# fat41.net
KiCad netlist of a schematic drawn in Altium Designer
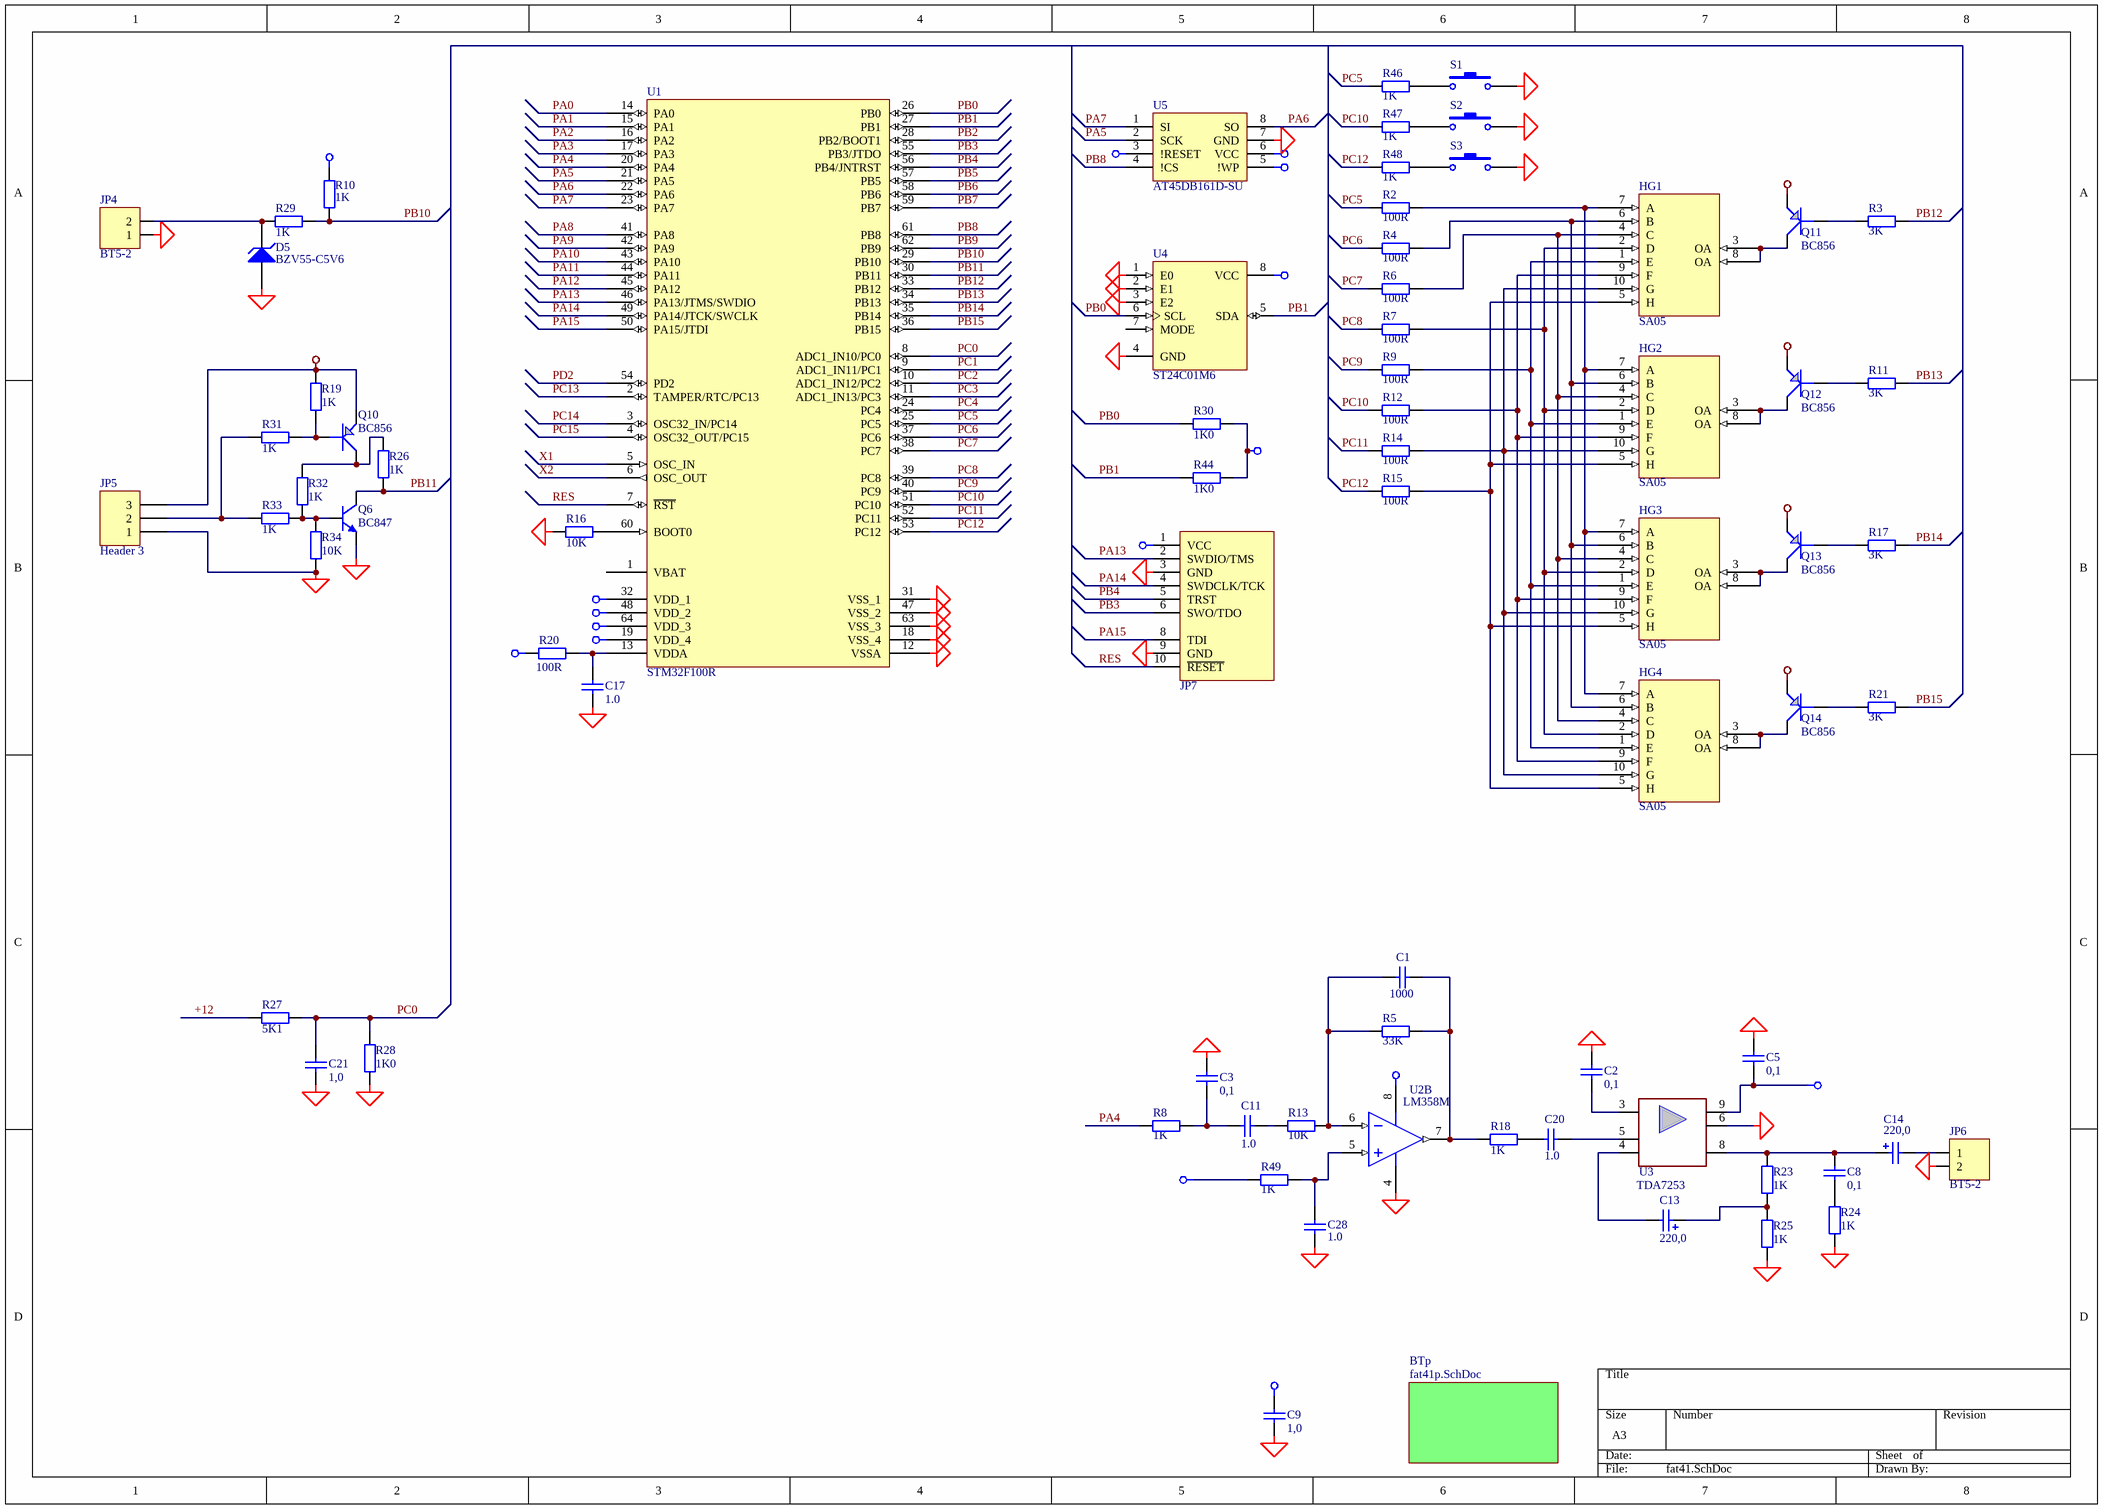
[diagram p0: fat41.SchDoc]

(export (version "E")
  (design (tool "Eeschema 10.0.6"))
  (components
    (comp (ref "C1")
      (value "Cap Semi")
      (footprint "_1206")
      (description "Capacitor (Semiconductor SIM Model)")
      (fields
        (field (name "MANUFACTURER") "Generic Components")
        (field (name "ALTIUM_VALUE") "1000")
        (field (name "PUBLISHER") "Altium Limited")
      )
      (libsource (lib "Miscellaneous Devices") (part "Cap Semi"))
    )
    (comp (ref "C2")
      (value "Cap Semi")
      (footprint "C3216-1206")
      (description "Capacitor (Semiconductor SIM Model)")
      (fields
        (field (name "MANUFACTURER") "Generic Components")
        (field (name "ALTIUM_VALUE") "0,1")
        (field (name "PUBLISHER") "Altium Limited")
      )
      (libsource (lib "Miscellaneous Devices") (part "Cap Semi"))
    )
    (comp (ref "C3")
      (value "Cap Semi")
      (footprint "_1206")
      (description "Capacitor (Semiconductor SIM Model)")
      (fields
        (field (name "MANUFACTURER") "Generic Components")
        (field (name "ALTIUM_VALUE") "0,1")
        (field (name "PUBLISHER") "Altium Limited")
      )
      (libsource (lib "") (part "Cap Semi_1"))
    )
    (comp (ref "C5")
      (value "Cap Semi")
      (footprint "C3216-1206")
      (description "Capacitor (Semiconductor SIM Model)")
      (fields
        (field (name "MANUFACTURER") "Generic Components")
        (field (name "ALTIUM_VALUE") "0,1")
        (field (name "PUBLISHER") "Altium Limited")
      )
      (libsource (lib "Miscellaneous Devices") (part "Cap Semi"))
    )
    (comp (ref "C8")
      (value "Cap Semi")
      (footprint "C3216-1206")
      (description "Capacitor (Semiconductor SIM Model)")
      (fields
        (field (name "MANUFACTURER") "Generic Components")
        (field (name "ALTIUM_VALUE") "0,1")
        (field (name "PUBLISHER") "Altium Limited")
      )
      (libsource (lib "Miscellaneous Devices") (part "Cap Semi"))
    )
    (comp (ref "C9")
      (value "Cap Semi")
      (footprint "C3216-1206")
      (description "Capacitor (Semiconductor SIM Model)")
      (fields
        (field (name "MANUFACTURER") "Generic Components")
        (field (name "ALTIUM_VALUE") "1,0")
        (field (name "PUBLISHER") "Altium Limited")
      )
      (libsource (lib "Miscellaneous Devices") (part "Cap Semi"))
    )
    (comp (ref "C11")
      (value "Cap Semi")
      (footprint "_1206")
      (description "Capacitor (Semiconductor SIM Model)")
      (fields
        (field (name "MANUFACTURER") "Generic Components")
        (field (name "ALTIUM_VALUE") "1.0")
        (field (name "PUBLISHER") "Altium Limited")
      )
      (libsource (lib "Miscellaneous Devices") (part "Cap Semi"))
    )
    (comp (ref "C13")
      (value "Cap Pol1")
      (footprint "el3")
      (description "Polarized Capacitor (Radial)")
      (fields
        (field (name "MANUFACTURER") "Generic Components")
        (field (name "ALTIUM_VALUE") "220,0")
        (field (name "PUBLISHER") "Altium Limited")
      )
      (libsource (lib "PAL") (part "Cap Pol1"))
    )
    (comp (ref "C14")
      (value "Cap Pol1")
      (footprint "el5")
      (description "Polarized Capacitor (Radial)")
      (fields
        (field (name "MANUFACTURER") "Generic Components")
        (field (name "ALTIUM_VALUE") "220,0")
        (field (name "PUBLISHER") "Altium Limited")
      )
      (libsource (lib "PAL") (part "Cap Pol1"))
    )
    (comp (ref "C17")
      (value "1.0")
      (footprint "_1206")
      (description "Capacitor (Semiconductor SIM Model)")
      (fields (field (name "MANUFACTURER") "Generic Components") (field (name "PUBLISHER") "Altium Limited"))
      (libsource (lib "") (part "Cap Semi_1"))
    )
    (comp (ref "C20")
      (value "Cap Semi")
      (footprint "_1206")
      (description "Capacitor (Semiconductor SIM Model)")
      (fields
        (field (name "MANUFACTURER") "Generic Components")
        (field (name "ALTIUM_VALUE") "1.0")
        (field (name "PUBLISHER") "Altium Limited")
      )
      (libsource (lib "Miscellaneous Devices") (part "Cap Semi"))
    )
    (comp (ref "C21")
      (value "Cap Semi")
      (footprint "_1206")
      (description "Capacitor (Semiconductor SIM Model)")
      (fields
        (field (name "MANUFACTURER") "Generic Components")
        (field (name "ALTIUM_VALUE") "1,0")
        (field (name "PUBLISHER") "Altium Limited")
      )
      (libsource (lib "Miscellaneous Devices") (part "Cap Semi"))
    )
    (comp (ref "C28")
      (value "Cap Semi")
      (footprint "_1206")
      (description "Capacitor (Semiconductor SIM Model)")
      (fields
        (field (name "MANUFACTURER") "Generic Components")
        (field (name "ALTIUM_VALUE") "1.0")
        (field (name "PUBLISHER") "Altium Limited")
      )
      (libsource (lib "") (part "Cap Semi_1"))
    )
    (comp (ref "D5")
      (value "BZV55-C5V6")
      (footprint "_1206d")
      (description "Zener Diode")
      (fields (field (name "MANUFACTURER") "Generic Components") (field (name "PUBLISHER") "Altium Limited"))
      (libsource (lib "Miscellaneous Devices") (part "D Zener"))
    )
    (comp (ref "HG1") (value "SA05") (footprint "DIP10") (libsource (lib "PAL") (part "SA05")))
    (comp (ref "HG2") (value "SA05") (footprint "DIP10") (libsource (lib "PAL") (part "SA05")))
    (comp (ref "HG3") (value "SA05") (footprint "DIP10") (libsource (lib "PAL") (part "SA05")))
    (comp (ref "HG4") (value "SA05") (footprint "DIP10") (libsource (lib "PAL") (part "SA05")))
    (comp (ref "JP4")
      (value "BT5-2")
      (footprint "BT5-2-1")
      (description "Header, 3-Pin")
      (fields (field (name "MANUFACTURER") "Generic Components") (field (name "PUBLISHER") "Altium Limited"))
      (libsource (lib "") (part "BT5-2_1"))
    )
    (comp (ref "JP5")
      (value "Header 3")
      (footprint "BT5-3")
      (description "Header, 3-Pin")
      (fields (field (name "MANUFACTURER") "Generic Components") (field (name "PUBLISHER") "Altium Limited"))
      (libsource (lib "Miscellaneous Connectors") (part "Header 3"))
    )
    (comp (ref "JP6")
      (value "BT5-2")
      (footprint "BT5-2-1")
      (description "Header, 3-Pin")
      (fields (field (name "MANUFACTURER") "Generic Components") (field (name "PUBLISHER") "Altium Limited"))
      (libsource (lib "PAL") (part "BT5-2"))
    )
    (comp (ref "JP7")
      (value "CORTEX_DEBUG_CONNECTOR_PAL")
      (footprint "CORTEX_DEBUG_CONNECTOR")
      (libsource (lib "PAL") (part "CORTEX_DEBUG_CONNECTOR_PAL"))
    )
    (comp (ref "Q6")
      (value "BC847")
      (footprint "SO-G3")
      (description "General Purpose Transistor NPN Silicon")
      (fields (field (name "MANUFACTURER") "Motorola") (field (name "PUBLISHER") "Altium Limited"))
      (libsource (lib "PAL") (part "BC847ALT1"))
    )
    (comp (ref "Q10") (value "BC856") (footprint "SO-G3") (libsource (lib "MAIN") (part "GT109")))
    (comp (ref "Q11") (value "BC856") (footprint "SO-G3") (libsource (lib "MAIN") (part "GT109")))
    (comp (ref "Q12") (value "BC856") (footprint "SO-G3") (libsource (lib "MAIN") (part "GT109")))
    (comp (ref "Q13") (value "BC856") (footprint "SO-G3") (libsource (lib "MAIN") (part "GT109")))
    (comp (ref "Q14") (value "BC856") (footprint "SO-G3") (libsource (lib "MAIN") (part "GT109")))
    (comp (ref "R2")
      (value "Res2")
      (footprint "_1206")
      (description "Resistor")
      (fields
        (field (name "MANUFACTURER") "Generic Components")
        (field (name "ALTIUM_VALUE") "100R")
        (field (name "PUBLISHER") "Altium Limited")
      )
      (libsource (lib "PAL") (part "RES"))
    )
    (comp (ref "R3")
      (value "Res2")
      (footprint "_1206")
      (description "Resistor")
      (fields
        (field (name "MANUFACTURER") "Generic Components")
        (field (name "ALTIUM_VALUE") "3K")
        (field (name "PUBLISHER") "Altium Limited")
      )
      (libsource (lib "PAL") (part "RES"))
    )
    (comp (ref "R4")
      (value "Res2")
      (footprint "_1206")
      (description "Resistor")
      (fields
        (field (name "MANUFACTURER") "Generic Components")
        (field (name "ALTIUM_VALUE") "100R")
        (field (name "PUBLISHER") "Altium Limited")
      )
      (libsource (lib "PAL") (part "RES"))
    )
    (comp (ref "R5")
      (value "Res2")
      (footprint "_1206")
      (description "Resistor")
      (fields
        (field (name "MANUFACTURER") "Generic Components")
        (field (name "ALTIUM_VALUE") "33K")
        (field (name "PUBLISHER") "Altium Limited")
      )
      (libsource (lib "") (part "Res2_1"))
    )
    (comp (ref "R6")
      (value "Res2")
      (footprint "_1206")
      (description "Resistor")
      (fields
        (field (name "MANUFACTURER") "Generic Components")
        (field (name "ALTIUM_VALUE") "100R")
        (field (name "PUBLISHER") "Altium Limited")
      )
      (libsource (lib "PAL") (part "RES"))
    )
    (comp (ref "R7")
      (value "Res2")
      (footprint "_1206")
      (description "Resistor")
      (fields
        (field (name "MANUFACTURER") "Generic Components")
        (field (name "ALTIUM_VALUE") "100R")
        (field (name "PUBLISHER") "Altium Limited")
      )
      (libsource (lib "PAL") (part "RES"))
    )
    (comp (ref "R8")
      (value "Res2")
      (footprint "_1206")
      (description "Resistor")
      (fields
        (field (name "MANUFACTURER") "Generic Components")
        (field (name "ALTIUM_VALUE") "1K")
        (field (name "PUBLISHER") "Altium Limited")
      )
      (libsource (lib "") (part "Res2_1"))
    )
    (comp (ref "R9")
      (value "Res2")
      (footprint "_1206")
      (description "Resistor")
      (fields
        (field (name "MANUFACTURER") "Generic Components")
        (field (name "ALTIUM_VALUE") "100R")
        (field (name "PUBLISHER") "Altium Limited")
      )
      (libsource (lib "PAL") (part "RES"))
    )
    (comp (ref "R10")
      (value "Res2")
      (footprint "_1206")
      (description "Resistor")
      (fields
        (field (name "MANUFACTURER") "Generic Components")
        (field (name "ALTIUM_VALUE") "1K")
        (field (name "PUBLISHER") "Altium Limited")
      )
      (libsource (lib "") (part "Res2_2"))
    )
    (comp (ref "R11")
      (value "Res2")
      (footprint "_1206")
      (description "Resistor")
      (fields
        (field (name "MANUFACTURER") "Generic Components")
        (field (name "ALTIUM_VALUE") "3K")
        (field (name "PUBLISHER") "Altium Limited")
      )
      (libsource (lib "PAL") (part "RES"))
    )
    (comp (ref "R12")
      (value "Res2")
      (footprint "_1206")
      (description "Resistor")
      (fields
        (field (name "MANUFACTURER") "Generic Components")
        (field (name "ALTIUM_VALUE") "100R")
        (field (name "PUBLISHER") "Altium Limited")
      )
      (libsource (lib "PAL") (part "RES"))
    )
    (comp (ref "R13")
      (value "Res2")
      (footprint "_1206")
      (description "Resistor")
      (fields
        (field (name "MANUFACTURER") "Generic Components")
        (field (name "ALTIUM_VALUE") "10K")
        (field (name "PUBLISHER") "Altium Limited")
      )
      (libsource (lib "") (part "Res2_1"))
    )
    (comp (ref "R14")
      (value "Res2")
      (footprint "_1206")
      (description "Resistor")
      (fields
        (field (name "MANUFACTURER") "Generic Components")
        (field (name "ALTIUM_VALUE") "100R")
        (field (name "PUBLISHER") "Altium Limited")
      )
      (libsource (lib "PAL") (part "RES"))
    )
    (comp (ref "R15")
      (value "Res2")
      (footprint "_1206")
      (description "Resistor")
      (fields
        (field (name "MANUFACTURER") "Generic Components")
        (field (name "ALTIUM_VALUE") "100R")
        (field (name "PUBLISHER") "Altium Limited")
      )
      (libsource (lib "PAL") (part "RES"))
    )
    (comp (ref "R16")
      (value "10K")
      (footprint "_1206")
      (description "Resistor")
      (fields (field (name "MANUFACTURER") "Generic Components") (field (name "PUBLISHER") "Altium Limited"))
      (libsource (lib "PAL") (part "RES"))
    )
    (comp (ref "R17")
      (value "Res2")
      (footprint "_1206")
      (description "Resistor")
      (fields
        (field (name "MANUFACTURER") "Generic Components")
        (field (name "ALTIUM_VALUE") "3K")
        (field (name "PUBLISHER") "Altium Limited")
      )
      (libsource (lib "PAL") (part "RES"))
    )
    (comp (ref "R18")
      (value "Res2")
      (footprint "_1206")
      (description "Resistor")
      (fields
        (field (name "MANUFACTURER") "Generic Components")
        (field (name "ALTIUM_VALUE") "1K")
        (field (name "PUBLISHER") "Altium Limited")
      )
      (libsource (lib "") (part "Res2_3"))
    )
    (comp (ref "R19")
      (value "Res2")
      (footprint "_1206")
      (description "Resistor")
      (fields
        (field (name "MANUFACTURER") "Generic Components")
        (field (name "ALTIUM_VALUE") "1K")
        (field (name "PUBLISHER") "Altium Limited")
      )
      (libsource (lib "PAL") (part "RES"))
    )
    (comp (ref "R20")
      (value "100R")
      (footprint "_1206")
      (description "Resistor")
      (fields (field (name "MANUFACTURER") "Generic Components") (field (name "PUBLISHER") "Altium Limited"))
      (libsource (lib "Miscellaneous Devices") (part "Res2"))
    )
    (comp (ref "R21")
      (value "Res2")
      (footprint "_1206")
      (description "Resistor")
      (fields
        (field (name "MANUFACTURER") "Generic Components")
        (field (name "ALTIUM_VALUE") "3K")
        (field (name "PUBLISHER") "Altium Limited")
      )
      (libsource (lib "PAL") (part "RES"))
    )
    (comp (ref "R23")
      (value "Res2")
      (footprint "_1206")
      (description "Resistor")
      (fields
        (field (name "MANUFACTURER") "Generic Components")
        (field (name "ALTIUM_VALUE") "1K")
        (field (name "PUBLISHER") "Altium Limited")
      )
      (libsource (lib "") (part "RES_2"))
    )
    (comp (ref "R24")
      (value "Res2")
      (footprint "_1206")
      (description "Resistor")
      (fields
        (field (name "MANUFACTURER") "Generic Components")
        (field (name "ALTIUM_VALUE") "1K")
        (field (name "PUBLISHER") "Altium Limited")
      )
      (libsource (lib "") (part "RES_2"))
    )
    (comp (ref "R25")
      (value "Res2")
      (footprint "_1206")
      (description "Resistor")
      (fields
        (field (name "MANUFACTURER") "Generic Components")
        (field (name "ALTIUM_VALUE") "1K")
        (field (name "PUBLISHER") "Altium Limited")
      )
      (libsource (lib "") (part "RES_2"))
    )
    (comp (ref "R26")
      (value "Res2")
      (footprint "_1206")
      (description "Resistor")
      (fields
        (field (name "MANUFACTURER") "Generic Components")
        (field (name "ALTIUM_VALUE") "1K")
        (field (name "PUBLISHER") "Altium Limited")
      )
      (libsource (lib "") (part "RES_1"))
    )
    (comp (ref "R27")
      (value "Res2")
      (footprint "_1206")
      (description "Resistor")
      (fields
        (field (name "MANUFACTURER") "Generic Components")
        (field (name "ALTIUM_VALUE") "5K1")
        (field (name "PUBLISHER") "Altium Limited")
      )
      (libsource (lib "Miscellaneous Devices") (part "Res2"))
    )
    (comp (ref "R28")
      (value "Res2")
      (footprint "_1206")
      (description "Resistor")
      (fields
        (field (name "MANUFACTURER") "Generic Components")
        (field (name "ALTIUM_VALUE") "1K0")
        (field (name "PUBLISHER") "Altium Limited")
      )
      (libsource (lib "") (part "Res2_2"))
    )
    (comp (ref "R29")
      (value "Res2")
      (footprint "_1206")
      (description "Resistor")
      (fields
        (field (name "MANUFACTURER") "Generic Components")
        (field (name "ALTIUM_VALUE") "1K")
        (field (name "PUBLISHER") "Altium Limited")
      )
      (libsource (lib "Miscellaneous Devices") (part "Res2"))
    )
    (comp (ref "R30")
      (value "1K0")
      (footprint "_1206")
      (description "Resistor")
      (fields (field (name "MANUFACTURER") "Generic Components") (field (name "PUBLISHER") "Altium Limited"))
      (libsource (lib "PAL") (part "RES"))
    )
    (comp (ref "R31")
      (value "Res2")
      (footprint "_1206")
      (description "Resistor")
      (fields
        (field (name "MANUFACTURER") "Generic Components")
        (field (name "ALTIUM_VALUE") "1K")
        (field (name "PUBLISHER") "Altium Limited")
      )
      (libsource (lib "Miscellaneous Devices") (part "Res2"))
    )
    (comp (ref "R32")
      (value "Res2")
      (footprint "_1206")
      (description "Resistor")
      (fields
        (field (name "MANUFACTURER") "Generic Components")
        (field (name "ALTIUM_VALUE") "1K")
        (field (name "PUBLISHER") "Altium Limited")
      )
      (libsource (lib "") (part "Res2_2"))
    )
    (comp (ref "R33")
      (value "Res2")
      (footprint "_1206")
      (description "Resistor")
      (fields
        (field (name "MANUFACTURER") "Generic Components")
        (field (name "ALTIUM_VALUE") "1K")
        (field (name "PUBLISHER") "Altium Limited")
      )
      (libsource (lib "Miscellaneous Devices") (part "Res2"))
    )
    (comp (ref "R34")
      (value "Res2")
      (footprint "_1206")
      (description "Resistor")
      (fields
        (field (name "MANUFACTURER") "Generic Components")
        (field (name "ALTIUM_VALUE") "10K")
        (field (name "PUBLISHER") "Altium Limited")
      )
      (libsource (lib "") (part "Res2_1"))
    )
    (comp (ref "R44")
      (value "1K0")
      (footprint "_1206")
      (description "Resistor")
      (fields (field (name "MANUFACTURER") "Generic Components") (field (name "PUBLISHER") "Altium Limited"))
      (libsource (lib "PAL") (part "RES"))
    )
    (comp (ref "R46")
      (value "Res2")
      (footprint "_1206")
      (description "Resistor")
      (fields
        (field (name "MANUFACTURER") "Generic Components")
        (field (name "ALTIUM_VALUE") "1K")
        (field (name "PUBLISHER") "Altium Limited")
      )
      (libsource (lib "PAL") (part "RES"))
    )
    (comp (ref "R47")
      (value "Res2")
      (footprint "_1206")
      (description "Resistor")
      (fields
        (field (name "MANUFACTURER") "Generic Components")
        (field (name "ALTIUM_VALUE") "1K")
        (field (name "PUBLISHER") "Altium Limited")
      )
      (libsource (lib "PAL") (part "RES"))
    )
    (comp (ref "R48")
      (value "Res2")
      (footprint "_1206")
      (description "Resistor")
      (fields
        (field (name "MANUFACTURER") "Generic Components")
        (field (name "ALTIUM_VALUE") "1K")
        (field (name "PUBLISHER") "Altium Limited")
      )
      (libsource (lib "PAL") (part "RES"))
    )
    (comp (ref "R49")
      (value "Res2")
      (footprint "_1206")
      (description "Resistor")
      (fields
        (field (name "MANUFACTURER") "Generic Components")
        (field (name "ALTIUM_VALUE") "1K")
        (field (name "PUBLISHER") "Altium Limited")
      )
      (libsource (lib "") (part "Res2_1"))
    )
    (comp (ref "S1")
      (value "SWT-6")
      (footprint "SWT-6-9")
      (description "Switch")
      (fields (field (name "MANUFACTURER") "Generic Components") (field (name "PUBLISHER") "Altium Limited"))
      (libsource (lib "PAL") (part "SWT-6"))
    )
    (comp (ref "S2")
      (value "SWT-6")
      (footprint "SWT-6-9")
      (description "Switch")
      (fields (field (name "MANUFACTURER") "Generic Components") (field (name "PUBLISHER") "Altium Limited"))
      (libsource (lib "PAL") (part "SWT-6"))
    )
    (comp (ref "S3")
      (value "SWT-6")
      (footprint "SWT-6-9")
      (description "Switch")
      (fields (field (name "MANUFACTURER") "Generic Components") (field (name "PUBLISHER") "Altium Limited"))
      (libsource (lib "PAL") (part "SWT-6"))
    )
    (comp (ref "U1")
      (value "STM32F100R")
      (footprint "F-QFP10X10-G64/N")
      (description "STM32 ARM-based 32-bit MCU with 64 Kbytes Flash, 64-pin LQFP, Industrial Temperature")
      (fields (field (name "PUBLISHER") "*"))
      (libsource (lib "PAL") (part "STM32F100R"))
    )
    (comp (ref "U2")
      (value "LM358M")
      (footprint "SO-G8")
      (description "Low-Power Dual Operational Amplifier")
      (fields
        (field (name "MANUFACTURER") "National Semiconductor")
        (field (name "PUBLISHER") "Altium Limited")
      )
      (libsource (lib "NSC Operational Amplifier") (part "LM358M"))
    )
    (comp (ref "U3") (value "TDA7253") (footprint "Clipwatt11") (libsource (lib "PAL") (part "TDA7253")))
    (comp (ref "U4")
      (value "ST24C01M6")
      (footprint "SO-G8")
      (description "Serial 1K (128 x 8) EEPROM")
      (fields (field (name "MANUFACTURER") "ST-Microelectronics") (field (name "PUBLISHER") "Altium Limited"))
      (libsource (lib "ST Memory EEPROM Serial") (part "ST24C01M6"))
    )
    (comp (ref "U5")
      (value "AT45DB161D-SU")
      (footprint "at45w")
      (libsource (lib "igorenja") (part "AT45DB161D-SU"))
    )
  )
  (nets
    (net (code "1") (name "+3v3") (class "Default")
      (node (ref "C9") (pin "2") (pinfunction "2_2") (pintype "passive"))
      (node (ref "JP7") (pin "1") (pinfunction "VCC_1") (pintype "passive"))
      (node (ref "Q11") (pin "2") (pinfunction "E_2") (pintype "passive"))
      (node (ref "Q12") (pin "2") (pinfunction "E_2") (pintype "passive"))
      (node (ref "Q13") (pin "2") (pinfunction "E_2") (pintype "passive"))
      (node (ref "Q14") (pin "2") (pinfunction "E_2") (pintype "passive"))
      (node (ref "R10") (pin "1") (pinfunction "1_1") (pintype "passive"))
      (node (ref "R20") (pin "2") (pinfunction "2_2") (pintype "passive"))
      (node (ref "R30") (pin "2") (pinfunction "2_2") (pintype "passive"))
      (node (ref "R44") (pin "2") (pinfunction "2_2") (pintype "passive"))
      (node (ref "R49") (pin "2") (pinfunction "2_2") (pintype "passive"))
      (node (ref "U1") (pin "19") (pinfunction "VDD_4_19") (pintype "power_in"))
      (node (ref "U1") (pin "32") (pinfunction "VDD_1_32") (pintype "power_in"))
      (node (ref "U1") (pin "48") (pinfunction "VDD_2_48") (pintype "power_in"))
      (node (ref "U1") (pin "64") (pinfunction "VDD_3_64") (pintype "power_in"))
      (node (ref "U4") (pin "8") (pinfunction "VCC_8") (pintype "power_in"))
      (node (ref "U5") (pin "3") (pinfunction "!RESET_3") (pintype "passive"))
      (node (ref "U5") (pin "5") (pinfunction "!WP_5") (pintype "passive"))
      (node (ref "U5") (pin "6") (pinfunction "VCC_6") (pintype "passive"))
    )
    (net (code "2") (name "+12v") (class "Default")
      (node (ref "C5") (pin "1") (pinfunction "1_1") (pintype "passive"))
      (node (ref "JP5") (pin "3") (pinfunction "3_3") (pintype "passive"))
      (node (ref "Q10") (pin "2") (pinfunction "E_2") (pintype "passive"))
      (node (ref "R19") (pin "2") (pinfunction "2_2") (pintype "passive"))
      (node (ref "U2") (pin "8") (pinfunction "V+_8") (pintype "power_in"))
      (node (ref "U3") (pin "9") (pintype "passive"))
    )
    (net (code "3") (name "/+12") (class "Default")
      (node (ref "R27") (pin "2") (pinfunction "2_2") (pintype "passive"))
    )
    (net (code "4") (name "/PA0") (class "Default")
      (node (ref "U1") (pin "14") (pinfunction "PA0_14") (pintype "bidirectional"))
    )
    (net (code "5") (name "/PA1") (class "Default")
      (node (ref "U1") (pin "15") (pinfunction "PA1_15") (pintype "bidirectional"))
    )
    (net (code "6") (name "/PA2") (class "Default")
      (node (ref "U1") (pin "16") (pinfunction "PA2_16") (pintype "bidirectional"))
    )
    (net (code "7") (name "/PA3") (class "Default")
      (node (ref "U1") (pin "17") (pinfunction "PA3_17") (pintype "bidirectional"))
    )
    (net (code "8") (name "/PA4") (class "Default")
      (node (ref "R8") (pin "2") (pinfunction "2_2") (pintype "passive"))
      (node (ref "U1") (pin "20") (pinfunction "PA4_20") (pintype "bidirectional"))
    )
    (net (code "9") (name "/PA5") (class "Default")
      (node (ref "U1") (pin "21") (pinfunction "PA5_21") (pintype "bidirectional"))
      (node (ref "U5") (pin "2") (pinfunction "SCK_2") (pintype "passive"))
    )
    (net (code "10") (name "/PA6") (class "Default")
      (node (ref "U1") (pin "22") (pinfunction "PA6_22") (pintype "bidirectional"))
      (node (ref "U5") (pin "8") (pinfunction "SO_8") (pintype "passive"))
    )
    (net (code "11") (name "/PA7") (class "Default")
      (node (ref "U1") (pin "23") (pinfunction "PA7_23") (pintype "bidirectional"))
      (node (ref "U5") (pin "1") (pinfunction "SI_1") (pintype "passive"))
    )
    (net (code "12") (name "/PA8") (class "Default")
      (node (ref "U1") (pin "41") (pinfunction "PA8_41") (pintype "bidirectional"))
    )
    (net (code "13") (name "/PA9") (class "Default")
      (node (ref "U1") (pin "42") (pinfunction "PA9_42") (pintype "bidirectional"))
    )
    (net (code "14") (name "/PA10") (class "Default")
      (node (ref "U1") (pin "43") (pinfunction "PA10_43") (pintype "bidirectional"))
    )
    (net (code "15") (name "/PA11") (class "Default")
      (node (ref "U1") (pin "44") (pinfunction "PA11_44") (pintype "bidirectional"))
    )
    (net (code "16") (name "/PA12") (class "Default")
      (node (ref "U1") (pin "45") (pinfunction "PA12_45") (pintype "bidirectional"))
    )
    (net (code "17") (name "/PA13") (class "Default")
      (node (ref "JP7") (pin "2") (pinfunction "SWDIO/TMS_2") (pintype "passive"))
      (node (ref "U1") (pin "46") (pinfunction "PA13/JTMS/SWDIO_46") (pintype "bidirectional"))
    )
    (net (code "18") (name "/PA14") (class "Default")
      (node (ref "JP7") (pin "4") (pinfunction "SWDCLK/TCK_4") (pintype "passive"))
      (node (ref "U1") (pin "49") (pinfunction "PA14/JTCK/SWCLK_49") (pintype "bidirectional"))
    )
    (net (code "19") (name "/PA15") (class "Default")
      (node (ref "JP7") (pin "8") (pinfunction "TDI_8") (pintype "passive"))
      (node (ref "U1") (pin "50") (pinfunction "PA15/JTDI_50") (pintype "bidirectional"))
    )
    (net (code "20") (name "/PB0") (class "Default")
      (node (ref "R30") (pin "1") (pinfunction "1_1") (pintype "passive"))
      (node (ref "U1") (pin "26") (pinfunction "PB0_26") (pintype "bidirectional"))
      (node (ref "U4") (pin "6") (pinfunction "SCL_6") (pintype "input"))
    )
    (net (code "21") (name "/PB1") (class "Default")
      (node (ref "R44") (pin "1") (pinfunction "1_1") (pintype "passive"))
      (node (ref "U1") (pin "27") (pinfunction "PB1_27") (pintype "bidirectional"))
      (node (ref "U4") (pin "5") (pinfunction "SDA_5") (pintype "bidirectional"))
    )
    (net (code "22") (name "/PB2") (class "Default")
      (node (ref "U1") (pin "28") (pinfunction "PB2/BOOT1_28") (pintype "bidirectional"))
    )
    (net (code "23") (name "/PB3") (class "Default")
      (node (ref "JP7") (pin "6") (pinfunction "SWO/TDO_6") (pintype "passive"))
      (node (ref "U1") (pin "55") (pinfunction "PB3/JTDO_55") (pintype "bidirectional"))
    )
    (net (code "24") (name "/PB4") (class "Default")
      (node (ref "JP7") (pin "5") (pinfunction "TRST_5") (pintype "passive"))
      (node (ref "U1") (pin "56") (pinfunction "PB4/JNTRST_56") (pintype "bidirectional"))
    )
    (net (code "25") (name "/PB5") (class "Default")
      (node (ref "U1") (pin "57") (pinfunction "PB5_57") (pintype "bidirectional"))
    )
    (net (code "26") (name "/PB6") (class "Default")
      (node (ref "U1") (pin "58") (pinfunction "PB6_58") (pintype "bidirectional"))
    )
    (net (code "27") (name "/PB7") (class "Default")
      (node (ref "U1") (pin "59") (pinfunction "PB7_59") (pintype "bidirectional"))
    )
    (net (code "28") (name "/PB8") (class "Default")
      (node (ref "U1") (pin "61") (pinfunction "PB8_61") (pintype "bidirectional"))
      (node (ref "U5") (pin "4") (pinfunction "!CS_4") (pintype "passive"))
    )
    (net (code "29") (name "/PB9") (class "Default")
      (node (ref "U1") (pin "62") (pinfunction "PB9_62") (pintype "bidirectional"))
    )
    (net (code "30") (name "/PB10") (class "Default")
      (node (ref "R10") (pin "2") (pinfunction "2_2") (pintype "passive"))
      (node (ref "R29") (pin "1") (pinfunction "1_1") (pintype "passive"))
      (node (ref "U1") (pin "29") (pinfunction "PB10_29") (pintype "bidirectional"))
    )
    (net (code "31") (name "/PB11") (class "Default")
      (node (ref "Q6") (pin "3") (pinfunction "C_3") (pintype "passive"))
      (node (ref "R26") (pin "2") (pinfunction "2_2") (pintype "passive"))
      (node (ref "U1") (pin "30") (pinfunction "PB11_30") (pintype "bidirectional"))
    )
    (net (code "32") (name "/PB12") (class "Default")
      (node (ref "R3") (pin "2") (pinfunction "2_2") (pintype "passive"))
      (node (ref "U1") (pin "33") (pinfunction "PB12_33") (pintype "bidirectional"))
    )
    (net (code "33") (name "/PB13") (class "Default")
      (node (ref "R11") (pin "2") (pinfunction "2_2") (pintype "passive"))
      (node (ref "U1") (pin "34") (pinfunction "PB13_34") (pintype "bidirectional"))
    )
    (net (code "34") (name "/PB14") (class "Default")
      (node (ref "R17") (pin "2") (pinfunction "2_2") (pintype "passive"))
      (node (ref "U1") (pin "35") (pinfunction "PB14_35") (pintype "bidirectional"))
    )
    (net (code "35") (name "/PB15") (class "Default")
      (node (ref "R21") (pin "2") (pinfunction "2_2") (pintype "passive"))
      (node (ref "U1") (pin "36") (pinfunction "PB15_36") (pintype "bidirectional"))
    )
    (net (code "36") (name "/PC0") (class "Default")
      (node (ref "C21") (pin "2") (pinfunction "2_2") (pintype "passive"))
      (node (ref "R27") (pin "1") (pinfunction "1_1") (pintype "passive"))
      (node (ref "R28") (pin "1") (pinfunction "1_1") (pintype "passive"))
      (node (ref "U1") (pin "8") (pinfunction "ADC1_IN10/PC0_8") (pintype "bidirectional"))
    )
    (net (code "37") (name "/PC1") (class "Default")
      (node (ref "U1") (pin "9") (pinfunction "ADC1_IN11/PC1_9") (pintype "bidirectional"))
    )
    (net (code "38") (name "/PC2") (class "Default")
      (node (ref "U1") (pin "10") (pinfunction "ADC1_IN12/PC2_10") (pintype "bidirectional"))
    )
    (net (code "39") (name "/PC3") (class "Default")
      (node (ref "U1") (pin "11") (pinfunction "ADC1_IN13/PC3_11") (pintype "bidirectional"))
    )
    (net (code "40") (name "/PC4") (class "Default")
      (node (ref "U1") (pin "24") (pinfunction "PC4_24") (pintype "bidirectional"))
    )
    (net (code "41") (name "/PC5") (class "Default")
      (node (ref "R2") (pin "1") (pinfunction "1_1") (pintype "passive"))
      (node (ref "R46") (pin "1") (pinfunction "1_1") (pintype "passive"))
      (node (ref "U1") (pin "25") (pinfunction "PC5_25") (pintype "bidirectional"))
    )
    (net (code "42") (name "/PC6") (class "Default")
      (node (ref "R4") (pin "1") (pinfunction "1_1") (pintype "passive"))
      (node (ref "U1") (pin "37") (pinfunction "PC6_37") (pintype "bidirectional"))
    )
    (net (code "43") (name "/PC7") (class "Default")
      (node (ref "R6") (pin "1") (pinfunction "1_1") (pintype "passive"))
      (node (ref "U1") (pin "38") (pinfunction "PC7_38") (pintype "bidirectional"))
    )
    (net (code "44") (name "/PC8") (class "Default")
      (node (ref "R7") (pin "1") (pinfunction "1_1") (pintype "passive"))
      (node (ref "U1") (pin "39") (pinfunction "PC8_39") (pintype "bidirectional"))
    )
    (net (code "45") (name "/PC9") (class "Default")
      (node (ref "R9") (pin "1") (pinfunction "1_1") (pintype "passive"))
      (node (ref "U1") (pin "40") (pinfunction "PC9_40") (pintype "bidirectional"))
    )
    (net (code "46") (name "/PC10") (class "Default")
      (node (ref "R12") (pin "1") (pinfunction "1_1") (pintype "passive"))
      (node (ref "R47") (pin "1") (pinfunction "1_1") (pintype "passive"))
      (node (ref "U1") (pin "51") (pinfunction "PC10_51") (pintype "bidirectional"))
    )
    (net (code "47") (name "/PC11") (class "Default")
      (node (ref "R14") (pin "1") (pinfunction "1_1") (pintype "passive"))
      (node (ref "U1") (pin "52") (pinfunction "PC11_52") (pintype "bidirectional"))
    )
    (net (code "48") (name "/PC12") (class "Default")
      (node (ref "R15") (pin "1") (pinfunction "1_1") (pintype "passive"))
      (node (ref "R48") (pin "1") (pinfunction "1_1") (pintype "passive"))
      (node (ref "U1") (pin "53") (pinfunction "PC12_53") (pintype "bidirectional"))
    )
    (net (code "49") (name "/PC13") (class "Default")
      (node (ref "U1") (pin "2") (pinfunction "TAMPER/RTC/PC13_2") (pintype "bidirectional"))
    )
    (net (code "50") (name "/PC14") (class "Default")
      (node (ref "U1") (pin "3") (pinfunction "OSC32_IN/PC14_3") (pintype "bidirectional"))
    )
    (net (code "51") (name "/PC15") (class "Default")
      (node (ref "U1") (pin "4") (pinfunction "OSC32_OUT/PC15_4") (pintype "bidirectional"))
    )
    (net (code "52") (name "/PD2") (class "Default")
      (node (ref "U1") (pin "54") (pinfunction "PD2_54") (pintype "bidirectional"))
    )
    (net (code "53") (name "/RES") (class "Default")
      (node (ref "JP7") (pin "10") (pinfunction "~{RESET}_10") (pintype "passive"))
      (node (ref "U1") (pin "7") (pinfunction "~{RST}_7") (pintype "bidirectional"))
    )
    (net (code "54") (name "/X1") (class "Default")
      (node (ref "U1") (pin "5") (pinfunction "OSC_IN_5") (pintype "input"))
    )
    (net (code "55") (name "/X2") (class "Default")
      (node (ref "U1") (pin "6") (pinfunction "OSC_OUT_6") (pintype "output"))
    )
    (net (code "56") (name "GND") (class "Default")
      (node (ref "C17") (pin "2") (pinfunction "2_2") (pintype "passive"))
      (node (ref "C2") (pin "2") (pinfunction "2_2") (pintype "passive"))
      (node (ref "C21") (pin "1") (pinfunction "1_1") (pintype "passive"))
      (node (ref "C28") (pin "2") (pinfunction "2_2") (pintype "passive"))
      (node (ref "C3") (pin "2") (pinfunction "2_2") (pintype "passive"))
      (node (ref "C5") (pin "2") (pinfunction "2_2") (pintype "passive"))
      (node (ref "C9") (pin "1") (pinfunction "1_1") (pintype "passive"))
      (node (ref "D5") (pin "1") (pinfunction "A_1") (pintype "passive"))
      (node (ref "JP4") (pin "1") (pinfunction "1_1") (pintype "passive"))
      (node (ref "JP5") (pin "1") (pinfunction "1_1") (pintype "passive"))
      (node (ref "JP6") (pin "2") (pinfunction "2_2") (pintype "passive"))
      (node (ref "JP7") (pin "3") (pinfunction "GND_3") (pintype "passive"))
      (node (ref "JP7") (pin "9") (pinfunction "GND_9") (pintype "passive"))
      (node (ref "Q6") (pin "2") (pinfunction "E_2") (pintype "passive"))
      (node (ref "R16") (pin "1") (pinfunction "1_1") (pintype "passive"))
      (node (ref "R24") (pin "1") (pinfunction "1_1") (pintype "passive"))
      (node (ref "R25") (pin "1") (pinfunction "1_1") (pintype "passive"))
      (node (ref "R28") (pin "2") (pinfunction "2_2") (pintype "passive"))
      (node (ref "R34") (pin "2") (pinfunction "2_2") (pintype "passive"))
      (node (ref "S1") (pin "2") (pinfunction "2_2") (pintype "passive"))
      (node (ref "S2") (pin "2") (pinfunction "2_2") (pintype "passive"))
      (node (ref "S3") (pin "2") (pinfunction "2_2") (pintype "passive"))
      (node (ref "U1") (pin "12") (pinfunction "VSSA_12") (pintype "power_in"))
      (node (ref "U1") (pin "18") (pinfunction "VSS_4_18") (pintype "power_in"))
      (node (ref "U1") (pin "31") (pinfunction "VSS_1_31") (pintype "power_in"))
      (node (ref "U1") (pin "47") (pinfunction "VSS_2_47") (pintype "power_in"))
      (node (ref "U1") (pin "63") (pinfunction "VSS_3_63") (pintype "power_in"))
      (node (ref "U2") (pin "4") (pinfunction "GND_4") (pintype "power_in"))
      (node (ref "U3") (pin "6") (pintype "passive"))
      (node (ref "U4") (pin "1") (pinfunction "E0_1") (pintype "input"))
      (node (ref "U4") (pin "2") (pinfunction "E1_2") (pintype "input"))
      (node (ref "U4") (pin "3") (pinfunction "E2_3") (pintype "input"))
      (node (ref "U4") (pin "4") (pinfunction "GND_4") (pintype "power_in"))
      (node (ref "U5") (pin "7") (pinfunction "GND_7") (pintype "passive"))
    )
    (net (code "57") (name "Net-(C8-Pad1)") (class "Default")
      (node (ref "C8") (pin "1") (pinfunction "1_1") (pintype "passive"))
      (node (ref "R24") (pin "2") (pinfunction "2_2") (pintype "passive"))
    )
    (net (code "58") (name "Net-(C11-Pad1)") (class "Default")
      (node (ref "C11") (pin "1") (pinfunction "1_1") (pintype "passive"))
      (node (ref "C3") (pin "1") (pinfunction "1_1") (pintype "passive"))
      (node (ref "R8") (pin "1") (pinfunction "1_1") (pintype "passive"))
    )
    (net (code "59") (name "Net-(C11-Pad2)") (class "Default")
      (node (ref "C11") (pin "2") (pinfunction "2_2") (pintype "passive"))
      (node (ref "R13") (pin "2") (pinfunction "2_2") (pintype "passive"))
    )
    (net (code "60") (name "Net-(C13-Pad1)") (class "Default")
      (node (ref "C13") (pin "1") (pinfunction "1_1") (pintype "passive"))
      (node (ref "R23") (pin "1") (pinfunction "1_1") (pintype "passive"))
      (node (ref "R25") (pin "2") (pinfunction "2_2") (pintype "passive"))
    )
    (net (code "61") (name "Net-(C13-Pad2)") (class "Default")
      (node (ref "C13") (pin "2") (pinfunction "2_2") (pintype "passive"))
      (node (ref "U3") (pin "4") (pintype "passive"))
    )
    (net (code "62") (name "Net-(C14-Pad1)") (class "Default")
      (node (ref "C14") (pin "1") (pinfunction "1_1") (pintype "passive"))
      (node (ref "C8") (pin "2") (pinfunction "2_2") (pintype "passive"))
      (node (ref "R23") (pin "2") (pinfunction "2_2") (pintype "passive"))
      (node (ref "U3") (pin "8") (pintype "passive"))
    )
    (net (code "63") (name "Net-(C14-Pad2)") (class "Default")
      (node (ref "C14") (pin "2") (pinfunction "2_2") (pintype "passive"))
      (node (ref "JP6") (pin "1") (pinfunction "1_1") (pintype "passive"))
    )
    (net (code "64") (name "Net-(C20-Pad1)") (class "Default")
      (node (ref "C20") (pin "1") (pinfunction "1_1") (pintype "passive"))
      (node (ref "R18") (pin "2") (pinfunction "2_2") (pintype "passive"))
    )
    (net (code "65") (name "Net-(D5-K)") (class "Default")
      (node (ref "D5") (pin "2") (pinfunction "K_2") (pintype "passive"))
      (node (ref "JP4") (pin "2") (pinfunction "2_2") (pintype "passive"))
      (node (ref "R29") (pin "2") (pinfunction "2_2") (pintype "passive"))
    )
    (net (code "66") (name "Net-(HG1-A)") (class "Default")
      (node (ref "HG1") (pin "7") (pinfunction "A_7") (pintype "input"))
      (node (ref "HG2") (pin "7") (pinfunction "A_7") (pintype "input"))
      (node (ref "HG3") (pin "7") (pinfunction "A_7") (pintype "input"))
      (node (ref "HG4") (pin "7") (pinfunction "A_7") (pintype "input"))
      (node (ref "R2") (pin "2") (pinfunction "2_2") (pintype "passive"))
    )
    (net (code "67") (name "Net-(HG1-B)") (class "Default")
      (node (ref "HG1") (pin "6") (pinfunction "B_6") (pintype "input"))
      (node (ref "HG2") (pin "6") (pinfunction "B_6") (pintype "input"))
      (node (ref "HG3") (pin "6") (pinfunction "B_6") (pintype "input"))
      (node (ref "HG4") (pin "6") (pinfunction "B_6") (pintype "input"))
      (node (ref "R4") (pin "2") (pinfunction "2_2") (pintype "passive"))
    )
    (net (code "68") (name "Net-(HG1-C)") (class "Default")
      (node (ref "HG1") (pin "4") (pinfunction "C_4") (pintype "input"))
      (node (ref "HG2") (pin "4") (pinfunction "C_4") (pintype "input"))
      (node (ref "HG3") (pin "4") (pinfunction "C_4") (pintype "input"))
      (node (ref "HG4") (pin "4") (pinfunction "C_4") (pintype "input"))
      (node (ref "R6") (pin "2") (pinfunction "2_2") (pintype "passive"))
    )
    (net (code "69") (name "Net-(HG1-D)") (class "Default")
      (node (ref "HG1") (pin "2") (pinfunction "D_2") (pintype "input"))
      (node (ref "HG2") (pin "2") (pinfunction "D_2") (pintype "input"))
      (node (ref "HG3") (pin "2") (pinfunction "D_2") (pintype "input"))
      (node (ref "HG4") (pin "2") (pinfunction "D_2") (pintype "input"))
      (node (ref "R7") (pin "2") (pinfunction "2_2") (pintype "passive"))
    )
    (net (code "70") (name "Net-(HG1-E)") (class "Default")
      (node (ref "HG1") (pin "1") (pinfunction "E_1") (pintype "input"))
      (node (ref "HG2") (pin "1") (pinfunction "E_1") (pintype "input"))
      (node (ref "HG3") (pin "1") (pinfunction "E_1") (pintype "input"))
      (node (ref "HG4") (pin "1") (pinfunction "E_1") (pintype "input"))
      (node (ref "R9") (pin "2") (pinfunction "2_2") (pintype "passive"))
    )
    (net (code "71") (name "Net-(HG1-F)") (class "Default")
      (node (ref "HG1") (pin "9") (pinfunction "F_9") (pintype "input"))
      (node (ref "HG2") (pin "9") (pinfunction "F_9") (pintype "input"))
      (node (ref "HG3") (pin "9") (pinfunction "F_9") (pintype "input"))
      (node (ref "HG4") (pin "9") (pinfunction "F_9") (pintype "input"))
      (node (ref "R12") (pin "2") (pinfunction "2_2") (pintype "passive"))
    )
    (net (code "72") (name "Net-(HG1-G)") (class "Default")
      (node (ref "HG1") (pin "10") (pinfunction "G_10") (pintype "input"))
      (node (ref "HG2") (pin "10") (pinfunction "G_10") (pintype "input"))
      (node (ref "HG3") (pin "10") (pinfunction "G_10") (pintype "input"))
      (node (ref "HG4") (pin "10") (pinfunction "G_10") (pintype "input"))
      (node (ref "R14") (pin "2") (pinfunction "2_2") (pintype "passive"))
    )
    (net (code "73") (name "Net-(HG1-H)") (class "Default")
      (node (ref "HG1") (pin "5") (pinfunction "H_5") (pintype "input"))
      (node (ref "HG2") (pin "5") (pinfunction "H_5") (pintype "input"))
      (node (ref "HG3") (pin "5") (pinfunction "H_5") (pintype "input"))
      (node (ref "HG4") (pin "5") (pinfunction "H_5") (pintype "input"))
      (node (ref "R15") (pin "2") (pinfunction "2_2") (pintype "passive"))
    )
    (net (code "74") (name "Net-(JP5-Pad2)") (class "Default")
      (node (ref "JP5") (pin "2") (pinfunction "2_2") (pintype "passive"))
      (node (ref "R31") (pin "2") (pinfunction "2_2") (pintype "passive"))
      (node (ref "R33") (pin "2") (pinfunction "2_2") (pintype "passive"))
    )
    (net (code "75") (name "Net-(Q6-B)") (class "Default")
      (node (ref "Q6") (pin "1") (pinfunction "B_1") (pintype "passive"))
      (node (ref "R32") (pin "2") (pinfunction "2_2") (pintype "passive"))
      (node (ref "R33") (pin "1") (pinfunction "1_1") (pintype "passive"))
      (node (ref "R34") (pin "1") (pinfunction "1_1") (pintype "passive"))
    )
    (net (code "76") (name "Net-(Q10-B)") (class "Default")
      (node (ref "Q10") (pin "1") (pinfunction "B_1") (pintype "passive"))
      (node (ref "R19") (pin "1") (pinfunction "1_1") (pintype "passive"))
      (node (ref "R31") (pin "1") (pinfunction "1_1") (pintype "passive"))
    )
    (net (code "77") (name "Net-(Q10-C)") (class "Default")
      (node (ref "Q10") (pin "3") (pinfunction "C_3") (pintype "passive"))
      (node (ref "R26") (pin "1") (pinfunction "1_1") (pintype "passive"))
      (node (ref "R32") (pin "1") (pinfunction "1_1") (pintype "passive"))
    )
    (net (code "78") (name "Net-(Q11-B)") (class "Default")
      (node (ref "Q11") (pin "1") (pinfunction "B_1") (pintype "passive"))
      (node (ref "R3") (pin "1") (pinfunction "1_1") (pintype "passive"))
    )
    (net (code "79") (name "Net-(Q11-C)") (class "Default")
      (node (ref "HG1") (pin "3") (pinfunction "OA_3") (pintype "input"))
      (node (ref "HG1") (pin "8") (pinfunction "OA_8") (pintype "input"))
      (node (ref "Q11") (pin "3") (pinfunction "C_3") (pintype "passive"))
    )
    (net (code "80") (name "Net-(Q12-B)") (class "Default")
      (node (ref "Q12") (pin "1") (pinfunction "B_1") (pintype "passive"))
      (node (ref "R11") (pin "1") (pinfunction "1_1") (pintype "passive"))
    )
    (net (code "81") (name "Net-(Q12-C)") (class "Default")
      (node (ref "HG2") (pin "3") (pinfunction "OA_3") (pintype "input"))
      (node (ref "HG2") (pin "8") (pinfunction "OA_8") (pintype "input"))
      (node (ref "Q12") (pin "3") (pinfunction "C_3") (pintype "passive"))
    )
    (net (code "82") (name "Net-(Q13-B)") (class "Default")
      (node (ref "Q13") (pin "1") (pinfunction "B_1") (pintype "passive"))
      (node (ref "R17") (pin "1") (pinfunction "1_1") (pintype "passive"))
    )
    (net (code "83") (name "Net-(Q13-C)") (class "Default")
      (node (ref "HG3") (pin "3") (pinfunction "OA_3") (pintype "input"))
      (node (ref "HG3") (pin "8") (pinfunction "OA_8") (pintype "input"))
      (node (ref "Q13") (pin "3") (pinfunction "C_3") (pintype "passive"))
    )
    (net (code "84") (name "Net-(Q14-B)") (class "Default")
      (node (ref "Q14") (pin "1") (pinfunction "B_1") (pintype "passive"))
      (node (ref "R21") (pin "1") (pinfunction "1_1") (pintype "passive"))
    )
    (net (code "85") (name "Net-(Q14-C)") (class "Default")
      (node (ref "HG4") (pin "3") (pinfunction "OA_3") (pintype "input"))
      (node (ref "HG4") (pin "8") (pinfunction "OA_8") (pintype "input"))
      (node (ref "Q14") (pin "3") (pinfunction "C_3") (pintype "passive"))
    )
    (net (code "86") (name "Net-(R46-Pad2)") (class "Default")
      (node (ref "R46") (pin "2") (pinfunction "2_2") (pintype "passive"))
      (node (ref "S1") (pin "1") (pinfunction "1_1") (pintype "passive"))
    )
    (net (code "87") (name "Net-(R47-Pad2)") (class "Default")
      (node (ref "R47") (pin "2") (pinfunction "2_2") (pintype "passive"))
      (node (ref "S2") (pin "1") (pinfunction "1_1") (pintype "passive"))
    )
    (net (code "88") (name "Net-(R48-Pad2)") (class "Default")
      (node (ref "R48") (pin "2") (pinfunction "2_2") (pintype "passive"))
      (node (ref "S3") (pin "1") (pinfunction "1_1") (pintype "passive"))
    )
    (net (code "89") (name "Net-(U1-BOOT0)") (class "Default")
      (node (ref "R16") (pin "2") (pinfunction "2_2") (pintype "passive"))
      (node (ref "U1") (pin "60") (pinfunction "BOOT0_60") (pintype "input"))
    )
    (net (code "90") (name "Net-(U1-VDDA)") (class "Default")
      (node (ref "C17") (pin "1") (pinfunction "1_1") (pintype "passive"))
      (node (ref "R20") (pin "1") (pinfunction "1_1") (pintype "passive"))
      (node (ref "U1") (pin "13") (pinfunction "VDDA_13") (pintype "power_in"))
    )
    (net (code "91") (name "Net-(U2B-IN+)") (class "Default")
      (node (ref "C28") (pin "1") (pinfunction "1_1") (pintype "passive"))
      (node (ref "R49") (pin "1") (pinfunction "1_1") (pintype "passive"))
      (node (ref "U2") (pin "5") (pinfunction "IN+_5") (pintype "input"))
    )
    (net (code "92") (name "Net-(U2B-IN-)") (class "Default")
      (node (ref "C1") (pin "2") (pinfunction "2_2") (pintype "passive"))
      (node (ref "R13") (pin "1") (pinfunction "1_1") (pintype "passive"))
      (node (ref "R5") (pin "2") (pinfunction "2_2") (pintype "passive"))
      (node (ref "U2") (pin "6") (pinfunction "IN-_6") (pintype "input"))
    )
    (net (code "93") (name "Net-(U2B-OUT)") (class "Default")
      (node (ref "C1") (pin "1") (pinfunction "1_1") (pintype "passive"))
      (node (ref "R18") (pin "1") (pinfunction "1_1") (pintype "passive"))
      (node (ref "R5") (pin "1") (pinfunction "1_1") (pintype "passive"))
      (node (ref "U2") (pin "7") (pinfunction "OUT_7") (pintype "output"))
    )
    (net (code "94") (name "Net-(U3-+)") (class "Default")
      (node (ref "C20") (pin "2") (pinfunction "2_2") (pintype "passive"))
      (node (ref "U3") (pin "5") (pinfunction "+_5") (pintype "passive"))
    )
    (net (code "95") (name "Net-(U3-MUTE)") (class "Default")
      (node (ref "C2") (pin "1") (pinfunction "1_1") (pintype "passive"))
      (node (ref "U3") (pin "3") (pinfunction "MUTE_3") (pintype "passive"))
    )
    (net (code "96") (name "unconnected-(U1-VBAT-Pad1)") (class "Default")
      (node (ref "U1") (pin "1") (pinfunction "VBAT_1") (pintype "power_in"))
    )
    (net (code "97") (name "unconnected-(U4-MODE-Pad7)") (class "Default")
      (node (ref "U4") (pin "7") (pinfunction "MODE_7") (pintype "input"))
    )
  )
)
